# KEY.net
KiCad netlist of a schematic drawn in Altium Designer
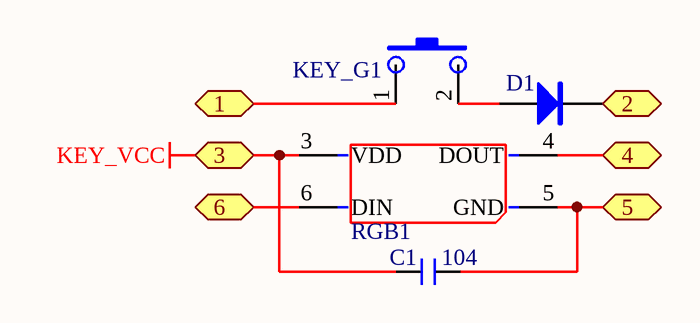
[diagram p0: KEY.SchDoc]

(export (version "E")
  (design (tool "Eeschema 10.0.6"))
  (components
    (comp (ref "C1")
      (value "104")
      (footprint "0805")
      (description "贴片电容")
      (libsource (lib "机械键盘") (part "C"))
    )
    (comp (ref "D1")
      (value "1N4148W-7-F")
      (footprint "SOD-123")
      (description "开关二极管")
      (libsource (lib "机械键盘") (part "1N4148"))
    )
    (comp (ref "KEY_G1")
      (value "KEY_G")
      (footprint "GATERON")
      (description "with Fixation pins  1-Pole w/Diode")
      (libsource (lib "机械键盘") (part "GATERON"))
    )
    (comp (ref "RGB1")
      (value "RGB")
      (footprint "WS2812")
      (description "with Fixation pins  1-Pole w/Diode")
      (libsource (lib "机械键盘") (part "WS2812"))
    )
  )
  (nets
    (net (code "1") (name "/1") (class "Default")
      (node (ref "KEY_G1") (pin "1") (pinfunction "1_1") (pintype "passive"))
    )
    (net (code "2") (name "/2") (class "Default")
      (node (ref "D1") (pin "2") (pinfunction "K_2") (pintype "passive"))
    )
    (net (code "3") (name "/4") (class "Default")
      (node (ref "RGB1") (pin "4") (pinfunction "DOUT_4") (pintype "passive"))
    )
    (net (code "4") (name "/5") (class "Default")
      (node (ref "C1") (pin "2") (pinfunction "2_2") (pintype "passive"))
      (node (ref "RGB1") (pin "5") (pinfunction "GND_5") (pintype "passive"))
    )
    (net (code "5") (name "/6") (class "Default")
      (node (ref "RGB1") (pin "6") (pinfunction "DIN_6") (pintype "passive"))
    )
    (net (code "6") (name "KEY_VCC") (class "Default")
      (node (ref "C1") (pin "1") (pinfunction "1_1") (pintype "passive"))
      (node (ref "RGB1") (pin "3") (pinfunction "VDD_3") (pintype "passive"))
    )
    (net (code "7") (name "Net-(D1-A)") (class "Default")
      (node (ref "D1") (pin "1") (pinfunction "A_1") (pintype "passive"))
      (node (ref "KEY_G1") (pin "2") (pinfunction "2_2") (pintype "passive"))
    )
  )
)
